# Power.net
KiCad netlist of a schematic drawn in Altium Designer
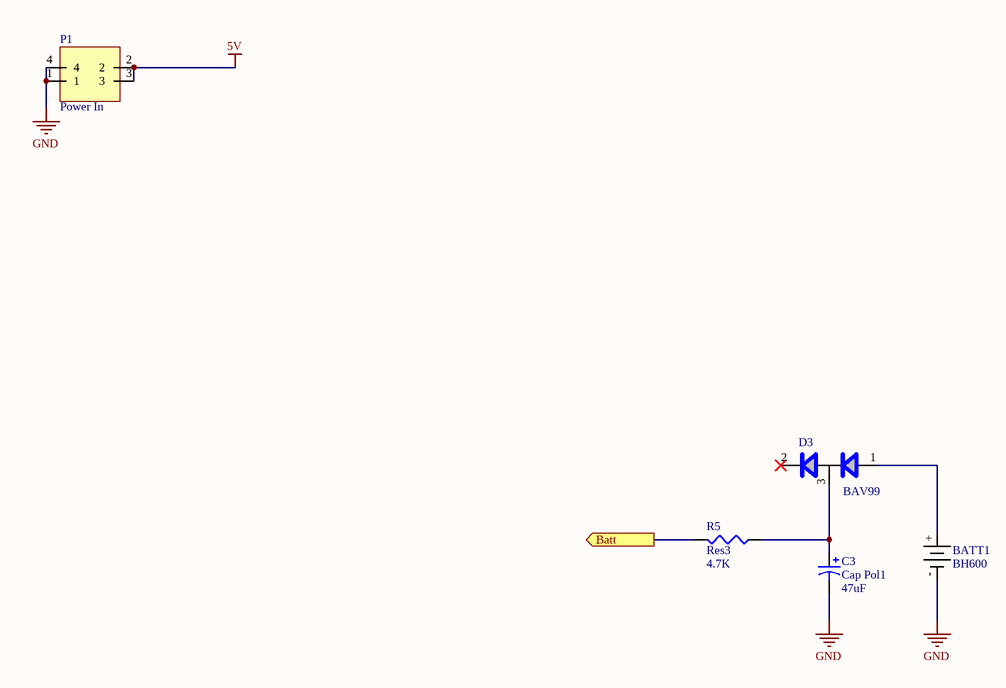
[diagram p0: Power.SchDoc]

(export (version "E")
  (design (tool "Eeschema 10.0.6"))
  (components
    (comp (ref "BATT1")
      (value "BH600")
      (footprint "BH600")
      (description "16mm Battery Holder - Memory Protection Devices")
      (libsource (lib "CoinBatteryHolders") (part "BH600"))
    )
    (comp (ref "C3")
      (value "Cap Pol1")
      (footprint "CAPPR5-5x5")
      (description "Polarized Capacitor (Radial)")
      (fields (field (name "ALTIUM_VALUE") "47uF") (field (name "PUBLISHER") "Altium Limited"))
      (libsource (lib "Miscellaneous Devices") (part "Cap Pol1"))
    )
    (comp (ref "D3")
      (value "BAV99")
      (footprint "SOT23")
      (description "Dual Surface Mount Switching Diode")
      (libsource (lib "Diodes") (part "BAV99"))
    )
    (comp (ref "P1")
      (value "Power In")
      (footprint "Molex:0039300040 MINI-FIT JR 4-Pos Right Angle")
      (libsource (lib "Molex") (part "0039300040 Mini-Fit 2x2 Right Angle"))
    )
    (comp (ref "R5")
      (value "Res3")
      (footprint "J1-0603")
      (description "Resistor")
      (fields (field (name "ALTIUM_VALUE") "4.7K") (field (name "PUBLISHER") "Altium Limited"))
      (libsource (lib "Miscellaneous Devices") (part "Res3"))
    )
  )
  (nets
    (net (code "1") (name "/Batt") (class "Default")
      (node (ref "R5") (pin "2") (pinfunction "2_2") (pintype "passive"))
    )
    (net (code "2") (name "5V") (class "Default")
      (node (ref "P1") (pin "2") (pinfunction "2_2") (pintype "passive"))
      (node (ref "P1") (pin "3") (pinfunction "3_3") (pintype "passive"))
    )
    (net (code "3") (name "GND") (class "Default")
      (node (ref "BATT1") (pin "-") (pinfunction "1_-") (pintype "passive"))
      (node (ref "C3") (pin "2") (pinfunction "2_2") (pintype "passive"))
      (node (ref "P1") (pin "1") (pinfunction "1_1") (pintype "passive"))
      (node (ref "P1") (pin "4") (pinfunction "4_4") (pintype "passive"))
    )
    (net (code "4") (name "Net-(BATT1-0)") (class "Default")
      (node (ref "BATT1") (pin "+") (pinfunction "0_+") (pintype "passive"))
      (node (ref "D3") (pin "1") (pinfunction "1_1") (pintype "passive"))
    )
    (net (code "5") (name "Net-(C3-Pad1)") (class "Default")
      (node (ref "C3") (pin "1") (pinfunction "1_1") (pintype "passive"))
      (node (ref "D3") (pin "3") (pinfunction "3_3") (pintype "passive"))
      (node (ref "R5") (pin "1") (pinfunction "1_1") (pintype "passive"))
    )
    (net (code "6") (name "unconnected-(D3-Pad2)") (class "Default")
      (node (ref "D3") (pin "2") (pinfunction "2_2") (pintype "passive+no_connect"))
    )
  )
)
